# Convert12to5.net
KiCad netlist of a schematic drawn in Altium Designer
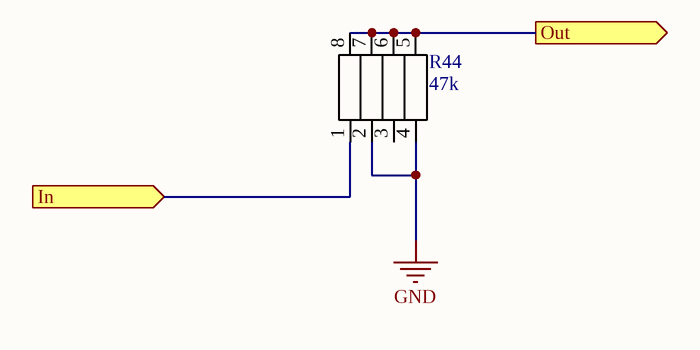
[diagram p0: Convert12to5.SchDoc]

(export (version "E")
  (design (tool "Eeschema 10.0.6"))
  (components
    (comp (ref "R44")
      (value "47k")
      (footprint "YC164")
      (description "YC164-JR-0747KL")
      (libsource (lib "Maks_lib") (part "YC164"))
    )
  )
  (nets
    (net (code "1") (name "/In") (class "Default")
      (node (ref "R44") (pin "1") (pinfunction "1_1") (pintype "passive"))
    )
    (net (code "2") (name "/Out") (class "Default")
      (node (ref "R44") (pin "5") (pinfunction "5_5") (pintype "passive"))
      (node (ref "R44") (pin "6") (pinfunction "6_6") (pintype "passive"))
      (node (ref "R44") (pin "7") (pinfunction "7_7") (pintype "passive"))
      (node (ref "R44") (pin "8") (pinfunction "8_8") (pintype "passive"))
    )
    (net (code "3") (name "GND") (class "Default")
      (node (ref "R44") (pin "2") (pinfunction "2_2") (pintype "passive"))
      (node (ref "R44") (pin "4") (pinfunction "4_4") (pintype "passive"))
    )
    (net (code "4") (name "unconnected-(R44-Pad3)") (class "Default")
      (node (ref "R44") (pin "3") (pinfunction "3_3") (pintype "passive"))
    )
  )
)
